# Schematic.net
KiCad netlist of a schematic drawn in EasyEDA
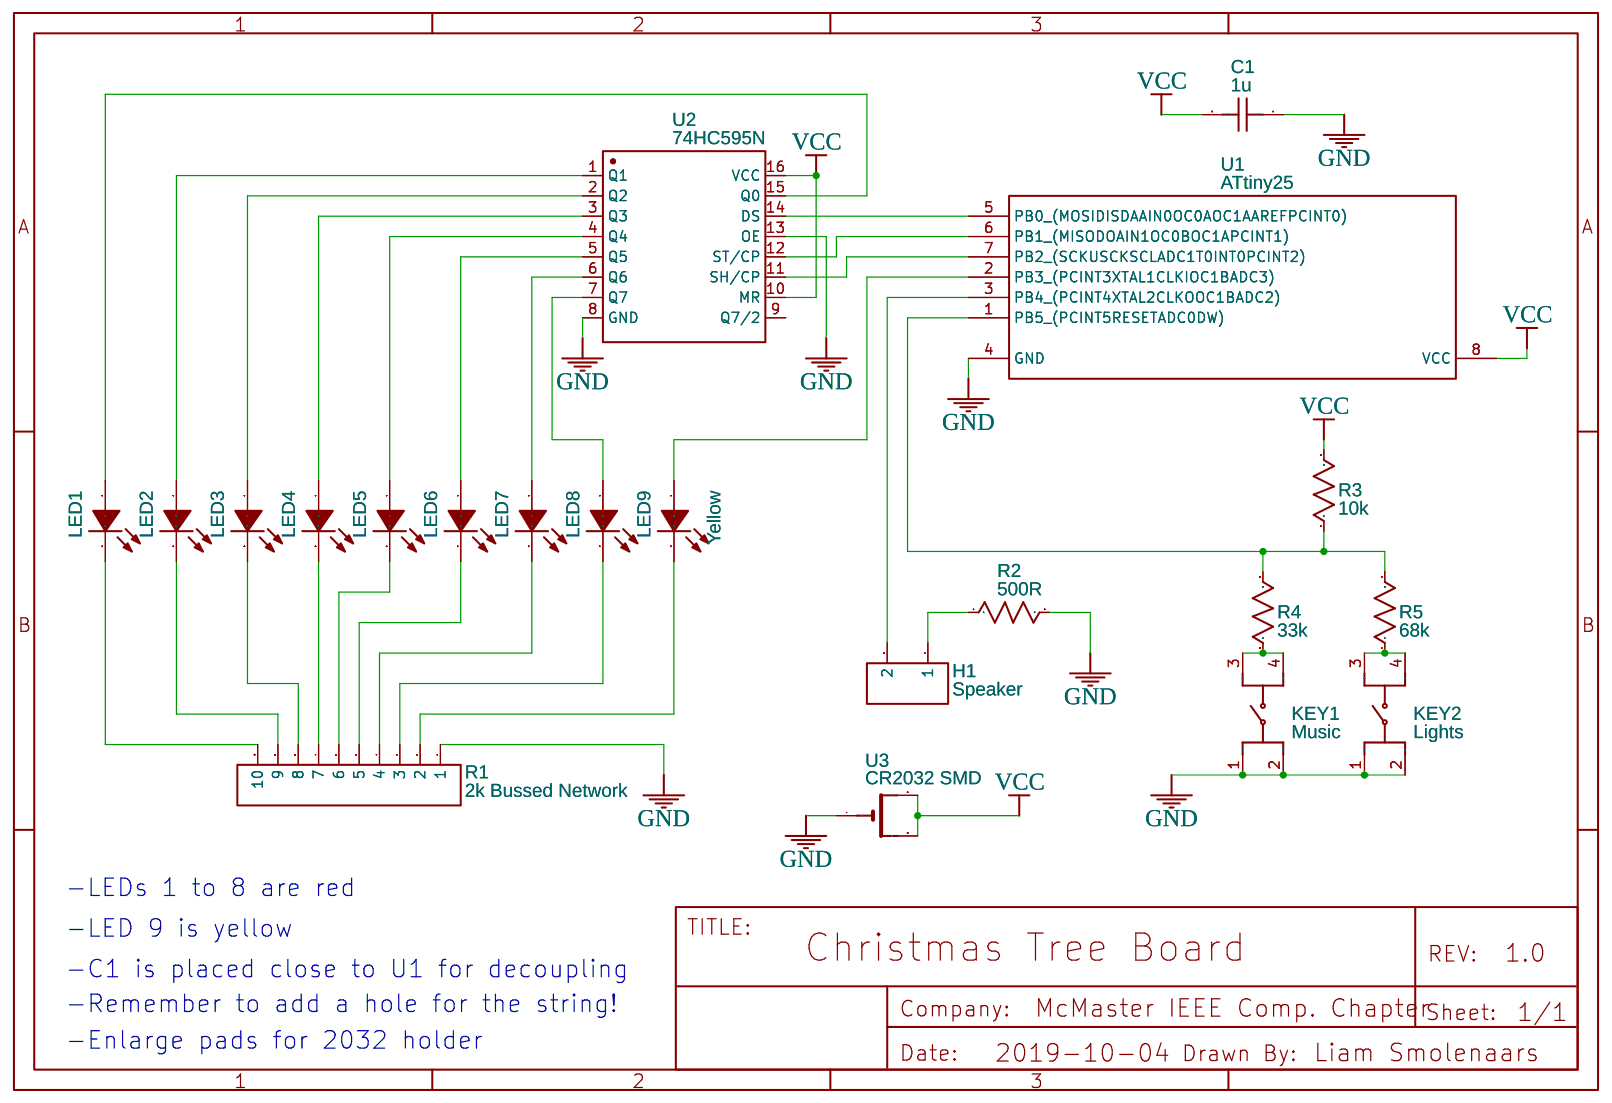
[diagram p0: schematic sheet]

(export (version "E")
  (design (tool "Eeschema 10.0.6"))
  (components
    (comp (ref "C1") (value "1u") (libsource (lib "") (part "Cap_RAD-0.1_US")))
    (comp (ref "H1")
      (value "Speaker")
      (fields (field (name "BOM_Manufacturer Part") "826629-2") (field (name "BOM_Supplier Part") "C86471"))
      (libsource (lib "") (part "Unknown_440_325"))
    )
    (comp (ref "KEY1")
      (value "Music")
      (fields
        (field (name "BOM_Manufacturer Part") "TS-1102-5016")
        (field (name "BOM_Supplier Part") "C111609")
      )
      (libsource (lib "") (part "Unknown_610_345"))
    )
    (comp (ref "KEY2")
      (value "Lights")
      (fields
        (field (name "BOM_Manufacturer Part") "TS-1102-5016")
        (field (name "BOM_Supplier Part") "C111609")
      )
      (libsource (lib "") (part "Unknown_670_345"))
    )
    (comp (ref "LED1")
      (value "204-10SURD/S530-A3")
      (fields (field (name "BOM_Supplier Part") "C99772"))
      (libsource (lib "") (part "Unknown_50_250"))
    )
    (comp (ref "LED2")
      (value "204-10SURD/S530-A3")
      (fields (field (name "BOM_Supplier Part") "C99772"))
      (libsource (lib "") (part "Unknown_85_250"))
    )
    (comp (ref "LED3")
      (value "204-10SURD/S530-A3")
      (fields (field (name "BOM_Supplier Part") "C99772"))
      (libsource (lib "") (part "Unknown_120_250"))
    )
    (comp (ref "LED4")
      (value "204-10SURD/S530-A3")
      (fields (field (name "BOM_Supplier Part") "C99772"))
      (libsource (lib "") (part "Unknown_155_250"))
    )
    (comp (ref "LED5")
      (value "204-10SURD/S530-A3")
      (fields (field (name "BOM_Supplier Part") "C99772"))
      (libsource (lib "") (part "Unknown_190_250"))
    )
    (comp (ref "LED6")
      (value "204-10SURD/S530-A3")
      (fields (field (name "BOM_Supplier Part") "C99772"))
      (libsource (lib "") (part "Unknown_225_250"))
    )
    (comp (ref "LED7")
      (value "204-10SURD/S530-A3")
      (fields (field (name "BOM_Supplier Part") "C99772"))
      (libsource (lib "") (part "Unknown_260_250"))
    )
    (comp (ref "LED8")
      (value "204-10SURD/S530-A3")
      (fields (field (name "BOM_Supplier Part") "C99772"))
      (libsource (lib "") (part "Unknown_295_250"))
    )
    (comp (ref "LED9")
      (value "Yellow")
      (fields
        (field (name "BOM_Manufacturer Part") "204-10SURD/S530-A3")
        (field (name "BOM_Supplier Part") "C99772")
      )
      (libsource (lib "") (part "Unknown_330_250"))
    )
    (comp (ref "R1")
      (value "2k Bussed Network")
      (fields
        (field (name "BOM_Manufacturer Part") "2.54mm 1*10P Straight Female header Gold-plated")
        (field (name "BOM_Supplier Part") "C35445")
      )
      (libsource (lib "") (part "Unknown_160_370"))
    )
    (comp (ref "R2") (value "500R") (libsource (lib "") (part "Res_0805(1/8W)_US_1")))
    (comp (ref "R3") (value "10k") (libsource (lib "") (part "Res_0805(1/8W)_US")))
    (comp (ref "R4") (value "33k") (libsource (lib "") (part "Res_0805(1/8W)_US")))
    (comp (ref "R5") (value "68k") (libsource (lib "") (part "Res_0805(1/8W)_US")))
    (comp (ref "U1") (value "ATtiny25") (libsource (lib "") (part "Unknown_600_135")))
    (comp (ref "U2") (value "74HC595N") (libsource (lib "") (part "Unknown_330_115")))
    (comp (ref "U3") (value "CR2032 SMD") (libsource (lib "") (part "Unknown_425_395")))
  )
  (nets
    (net (code "1") (name "GND") (class "Default")
      (node (ref "C1") (pin "1") (pinfunction "1_1") (pintype "unspecified"))
      (node (ref "KEY1") (pin "1") (pinfunction "1_1") (pintype "unspecified"))
      (node (ref "KEY1") (pin "2") (pinfunction "2_2") (pintype "unspecified"))
      (node (ref "KEY2") (pin "1") (pinfunction "1_1") (pintype "unspecified"))
      (node (ref "KEY2") (pin "2") (pinfunction "2_2") (pintype "unspecified"))
      (node (ref "R1") (pin "1") (pinfunction "1_1") (pintype "input"))
      (node (ref "R2") (pin "2") (pinfunction "2_2") (pintype "unspecified"))
      (node (ref "U1") (pin "4") (pinfunction "GND_4") (pintype "passive"))
      (node (ref "U2") (pin "13") (pinfunction "OE_13") (pintype "unspecified"))
      (node (ref "U2") (pin "8") (pinfunction "GND_8") (pintype "unspecified"))
      (node (ref "U3") (pin "-") (pinfunction "-_-") (pintype "unspecified"))
    )
    (net (code "2") (name "Net-(H1-Pad1)") (class "Default")
      (node (ref "H1") (pin "1") (pinfunction "1_1") (pintype "unspecified"))
      (node (ref "R2") (pin "1") (pinfunction "1_1") (pintype "unspecified"))
    )
    (net (code "3") (name "Net-(KEY1-Pad3)") (class "Default")
      (node (ref "KEY1") (pin "3") (pinfunction "3_3") (pintype "unspecified"))
      (node (ref "KEY1") (pin "4") (pinfunction "4_4") (pintype "unspecified"))
      (node (ref "R4") (pin "1") (pinfunction "1_1") (pintype "unspecified"))
    )
    (net (code "4") (name "Net-(KEY2-Pad3)") (class "Default")
      (node (ref "KEY2") (pin "3") (pinfunction "3_3") (pintype "unspecified"))
      (node (ref "KEY2") (pin "4") (pinfunction "4_4") (pintype "unspecified"))
      (node (ref "R5") (pin "1") (pinfunction "1_1") (pintype "unspecified"))
    )
    (net (code "5") (name "Net-(LED1-A)") (class "Default")
      (node (ref "LED1") (pin "1") (pinfunction "A_1") (pintype "unspecified"))
      (node (ref "U2") (pin "15") (pinfunction "Q0_15") (pintype "unspecified"))
    )
    (net (code "6") (name "Net-(LED1-K)") (class "Default")
      (node (ref "LED1") (pin "2") (pinfunction "K_2") (pintype "unspecified"))
      (node (ref "R1") (pin "10") (pinfunction "10_10") (pintype "input"))
    )
    (net (code "7") (name "Net-(LED2-A)") (class "Default")
      (node (ref "LED2") (pin "1") (pinfunction "A_1") (pintype "unspecified"))
      (node (ref "U2") (pin "1") (pinfunction "Q1_1") (pintype "unspecified"))
    )
    (net (code "8") (name "Net-(LED2-K)") (class "Default")
      (node (ref "LED2") (pin "2") (pinfunction "K_2") (pintype "unspecified"))
      (node (ref "R1") (pin "9") (pinfunction "9_9") (pintype "input"))
    )
    (net (code "9") (name "Net-(LED3-A)") (class "Default")
      (node (ref "LED3") (pin "1") (pinfunction "A_1") (pintype "unspecified"))
      (node (ref "U2") (pin "2") (pinfunction "Q2_2") (pintype "unspecified"))
    )
    (net (code "10") (name "Net-(LED3-K)") (class "Default")
      (node (ref "LED3") (pin "2") (pinfunction "K_2") (pintype "unspecified"))
      (node (ref "R1") (pin "8") (pinfunction "8_8") (pintype "input"))
    )
    (net (code "11") (name "Net-(LED4-A)") (class "Default")
      (node (ref "LED4") (pin "1") (pinfunction "A_1") (pintype "unspecified"))
      (node (ref "U2") (pin "3") (pinfunction "Q3_3") (pintype "unspecified"))
    )
    (net (code "12") (name "Net-(LED4-K)") (class "Default")
      (node (ref "LED4") (pin "2") (pinfunction "K_2") (pintype "unspecified"))
      (node (ref "R1") (pin "7") (pinfunction "7_7") (pintype "input"))
    )
    (net (code "13") (name "Net-(LED5-A)") (class "Default")
      (node (ref "LED5") (pin "1") (pinfunction "A_1") (pintype "unspecified"))
      (node (ref "U2") (pin "4") (pinfunction "Q4_4") (pintype "unspecified"))
    )
    (net (code "14") (name "Net-(LED5-K)") (class "Default")
      (node (ref "LED5") (pin "2") (pinfunction "K_2") (pintype "unspecified"))
      (node (ref "R1") (pin "6") (pinfunction "6_6") (pintype "input"))
    )
    (net (code "15") (name "Net-(LED6-A)") (class "Default")
      (node (ref "LED6") (pin "1") (pinfunction "A_1") (pintype "unspecified"))
      (node (ref "U2") (pin "5") (pinfunction "Q5_5") (pintype "unspecified"))
    )
    (net (code "16") (name "Net-(LED6-K)") (class "Default")
      (node (ref "LED6") (pin "2") (pinfunction "K_2") (pintype "unspecified"))
      (node (ref "R1") (pin "5") (pinfunction "5_5") (pintype "input"))
    )
    (net (code "17") (name "Net-(LED7-A)") (class "Default")
      (node (ref "LED7") (pin "1") (pinfunction "A_1") (pintype "unspecified"))
      (node (ref "U2") (pin "6") (pinfunction "Q6_6") (pintype "unspecified"))
    )
    (net (code "18") (name "Net-(LED7-K)") (class "Default")
      (node (ref "LED7") (pin "2") (pinfunction "K_2") (pintype "unspecified"))
      (node (ref "R1") (pin "4") (pinfunction "4_4") (pintype "input"))
    )
    (net (code "19") (name "Net-(LED8-A)") (class "Default")
      (node (ref "LED8") (pin "1") (pinfunction "A_1") (pintype "unspecified"))
      (node (ref "U2") (pin "7") (pinfunction "Q7_7") (pintype "unspecified"))
    )
    (net (code "20") (name "Net-(LED8-K)") (class "Default")
      (node (ref "LED8") (pin "2") (pinfunction "K_2") (pintype "unspecified"))
      (node (ref "R1") (pin "3") (pinfunction "3_3") (pintype "input"))
    )
    (net (code "21") (name "Net-(LED9-A)") (class "Default")
      (node (ref "LED9") (pin "1") (pinfunction "A_1") (pintype "unspecified"))
      (node (ref "U1") (pin "2") (pinfunction "PB3_(PCINT3XTAL1CLKIOC1BADC3)_2") (pintype "bidirectional"))
    )
    (net (code "22") (name "Net-(LED9-K)") (class "Default")
      (node (ref "LED9") (pin "2") (pinfunction "K_2") (pintype "unspecified"))
      (node (ref "R1") (pin "2") (pinfunction "2_2") (pintype "input"))
    )
    (net (code "23") (name "Net-(U1-PB0_(MOSIDISDAAIN0OC0AOC1AAREFPCINT0))") (class "Default")
      (node (ref "U1") (pin "5") (pinfunction "PB0_(MOSIDISDAAIN0OC0AOC1AAREFPCINT0)_5") (pintype "bidirectional"))
      (node (ref "U2") (pin "14") (pinfunction "DS_14") (pintype "unspecified"))
    )
    (net (code "24") (name "Net-(U1-PB1_(MISODOAIN1OC0BOC1APCINT1))") (class "Default")
      (node (ref "U1") (pin "6") (pinfunction "PB1_(MISODOAIN1OC0BOC1APCINT1)_6") (pintype "bidirectional"))
      (node (ref "U2") (pin "12") (pinfunction "ST/CP_12") (pintype "unspecified"))
    )
    (net (code "25") (name "Net-(U1-PB2_(SCKUSCKSCLADC1T0INT0PCINT2))") (class "Default")
      (node (ref "U1") (pin "7") (pinfunction "PB2_(SCKUSCKSCLADC1T0INT0PCINT2)_7") (pintype "bidirectional"))
      (node (ref "U2") (pin "11") (pinfunction "SH/CP_11") (pintype "unspecified"))
    )
    (net (code "26") (name "Net-(U1-PB4_(PCINT4XTAL2CLKOOC1BADC2))") (class "Default")
      (node (ref "H1") (pin "2") (pinfunction "2_2") (pintype "unspecified"))
      (node (ref "U1") (pin "3") (pinfunction "PB4_(PCINT4XTAL2CLKOOC1BADC2)_3") (pintype "bidirectional"))
    )
    (net (code "27") (name "Net-(U1-PB5_(PCINT5RESETADC0DW))") (class "Default")
      (node (ref "R3") (pin "1") (pinfunction "1_1") (pintype "unspecified"))
      (node (ref "R4") (pin "2") (pinfunction "2_2") (pintype "unspecified"))
      (node (ref "R5") (pin "2") (pinfunction "2_2") (pintype "unspecified"))
      (node (ref "U1") (pin "1") (pinfunction "PB5_(PCINT5RESETADC0DW)_1") (pintype "bidirectional"))
    )
    (net (code "28") (name "VCC") (class "Default")
      (node (ref "C1") (pin "2") (pinfunction "2_2") (pintype "unspecified"))
      (node (ref "R3") (pin "2") (pinfunction "2_2") (pintype "unspecified"))
      (node (ref "U1") (pin "8") (pinfunction "VCC_8") (pintype "passive"))
      (node (ref "U2") (pin "10") (pinfunction "MR_10") (pintype "unspecified"))
      (node (ref "U2") (pin "16") (pinfunction "VCC_16") (pintype "unspecified"))
      (node (ref "U3") (pin "+1") (pinfunction "+_+1") (pintype "unspecified"))
      (node (ref "U3") (pin "+2") (pinfunction "+1_+2") (pintype "unspecified"))
    )
    (net (code "29") (name "unconnected-(U2-Q7{slash}2-Pad9)") (class "Default")
      (node (ref "U2") (pin "9") (pinfunction "Q7/2_9") (pintype "unspecified"))
    )
  )
)
